# Input.net
KiCad netlist of a schematic drawn in Altium Designer
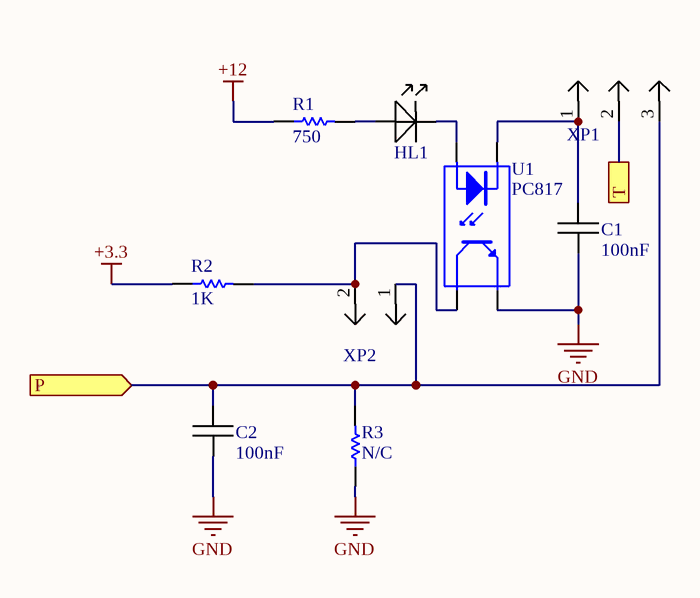
[diagram p0: Input.SchDoc]

(export (version "E")
  (design (tool "Eeschema 10.0.6"))
  (components
    (comp (ref "C1")
      (value "CAP_SMD")
      (footprint "CAP0805")
      (description "Ceramic capacitor, 0805")
      (fields (field (name "VAL") "100nF"))
      (libsource (lib "altium-import") (part "root_1_CAP_SMD_"))
    )
    (comp (ref "C2")
      (value "CAP_SMD")
      (footprint "CAP0805")
      (description "Ceramic capacitor, 0805")
      (fields (field (name "VAL") "100nF"))
      (libsource (lib "altium-import") (part "root_1_CAP_SMD_"))
    )
    (comp (ref "HL1")
      (value "LED_SMD")
      (footprint "0805_LED")
      (description "0805 led")
      (libsource (lib "altium-import") (part "root_0_LED_SMD_"))
    )
    (comp (ref "R1")
      (value "RES_SMD")
      (footprint "RES0805")
      (fields (field (name "VAL") "750"))
      (libsource (lib "altium-import") (part "root_0_RES_SMD_"))
    )
    (comp (ref "R2")
      (value "RES_SMD")
      (footprint "RES0805")
      (fields (field (name "VAL") "1K"))
      (libsource (lib "altium-import") (part "root_0_RES_SMD_"))
    )
    (comp (ref "R3")
      (value "RES_SMD")
      (footprint "RES0805")
      (fields (field (name "VAL") "N/C"))
      (libsource (lib "altium-import") (part "root_1_RES_SMD_"))
    )
    (comp (ref "U1")
      (value "PC817")
      (footprint "DIP-4 - SMT")
      (description "4-Pin Phototransistor Optocoupler")
      (fields (field (name "PUBLISHER") "Altium Limited"))
      (libsource (lib "altium-import") (part "root_3_mirrored_PC817_"))
    )
    (comp (ref "XP1")
      (value "PLS-03")
      (footprint "PLS-03")
      (libsource (lib "altium-import") (part "root_1_PLS-03_"))
    )
    (comp (ref "XP2")
      (value "PLS-02")
      (footprint "PLS-02")
      (libsource (lib "altium-import") (part "root_3_PLS-02_"))
    )
  )
  (nets
    (net (code "1") (name "+3.3") (class "Default")
      (node (ref "R2") (pin "1") (pinfunction "1_1") (pintype "passive"))
    )
    (net (code "2") (name "+12") (class "Default")
      (node (ref "R1") (pin "1") (pinfunction "1_1") (pintype "passive"))
    )
    (net (code "3") (name "/P") (class "Default")
      (node (ref "C2") (pin "2") (pinfunction "2_2") (pintype "passive"))
      (node (ref "R3") (pin "2") (pinfunction "2_2") (pintype "passive"))
      (node (ref "XP1") (pin "3") (pinfunction "3_3") (pintype "passive"))
      (node (ref "XP2") (pin "1") (pinfunction "1_1") (pintype "passive"))
    )
    (net (code "4") (name "/T") (class "Default")
      (node (ref "XP1") (pin "2") (pinfunction "2_2") (pintype "passive"))
    )
    (net (code "5") (name "GND") (class "Default")
      (node (ref "C1") (pin "1") (pinfunction "1_1") (pintype "passive"))
      (node (ref "C2") (pin "1") (pinfunction "1_1") (pintype "passive"))
      (node (ref "R3") (pin "1") (pinfunction "1_1") (pintype "passive"))
      (node (ref "U1") (pin "3") (pinfunction "E_3") (pintype "passive"))
    )
    (net (code "6") (name "Net-(HL1-anode)") (class "Default")
      (node (ref "HL1") (pin "1") (pinfunction "anode_1") (pintype "passive"))
      (node (ref "R1") (pin "2") (pinfunction "2_2") (pintype "passive"))
    )
    (net (code "7") (name "Net-(HL1-cathode)") (class "Default")
      (node (ref "HL1") (pin "2") (pinfunction "cathode_2") (pintype "passive"))
      (node (ref "U1") (pin "1") (pinfunction "A_1") (pintype "passive"))
    )
    (net (code "8") (name "Net-(U1-C)") (class "Default")
      (node (ref "R2") (pin "2") (pinfunction "2_2") (pintype "passive"))
      (node (ref "U1") (pin "4") (pinfunction "C_4") (pintype "passive"))
      (node (ref "XP2") (pin "2") (pinfunction "2_2") (pintype "passive"))
    )
    (net (code "9") (name "Net-(U1-K)") (class "Default")
      (node (ref "C1") (pin "2") (pinfunction "2_2") (pintype "passive"))
      (node (ref "U1") (pin "2") (pinfunction "K_2") (pintype "passive"))
      (node (ref "XP1") (pin "1") (pinfunction "1_1") (pintype "passive"))
    )
  )
)
